# TvsTester.net
KiCad netlist of a schematic drawn in Altium Designer
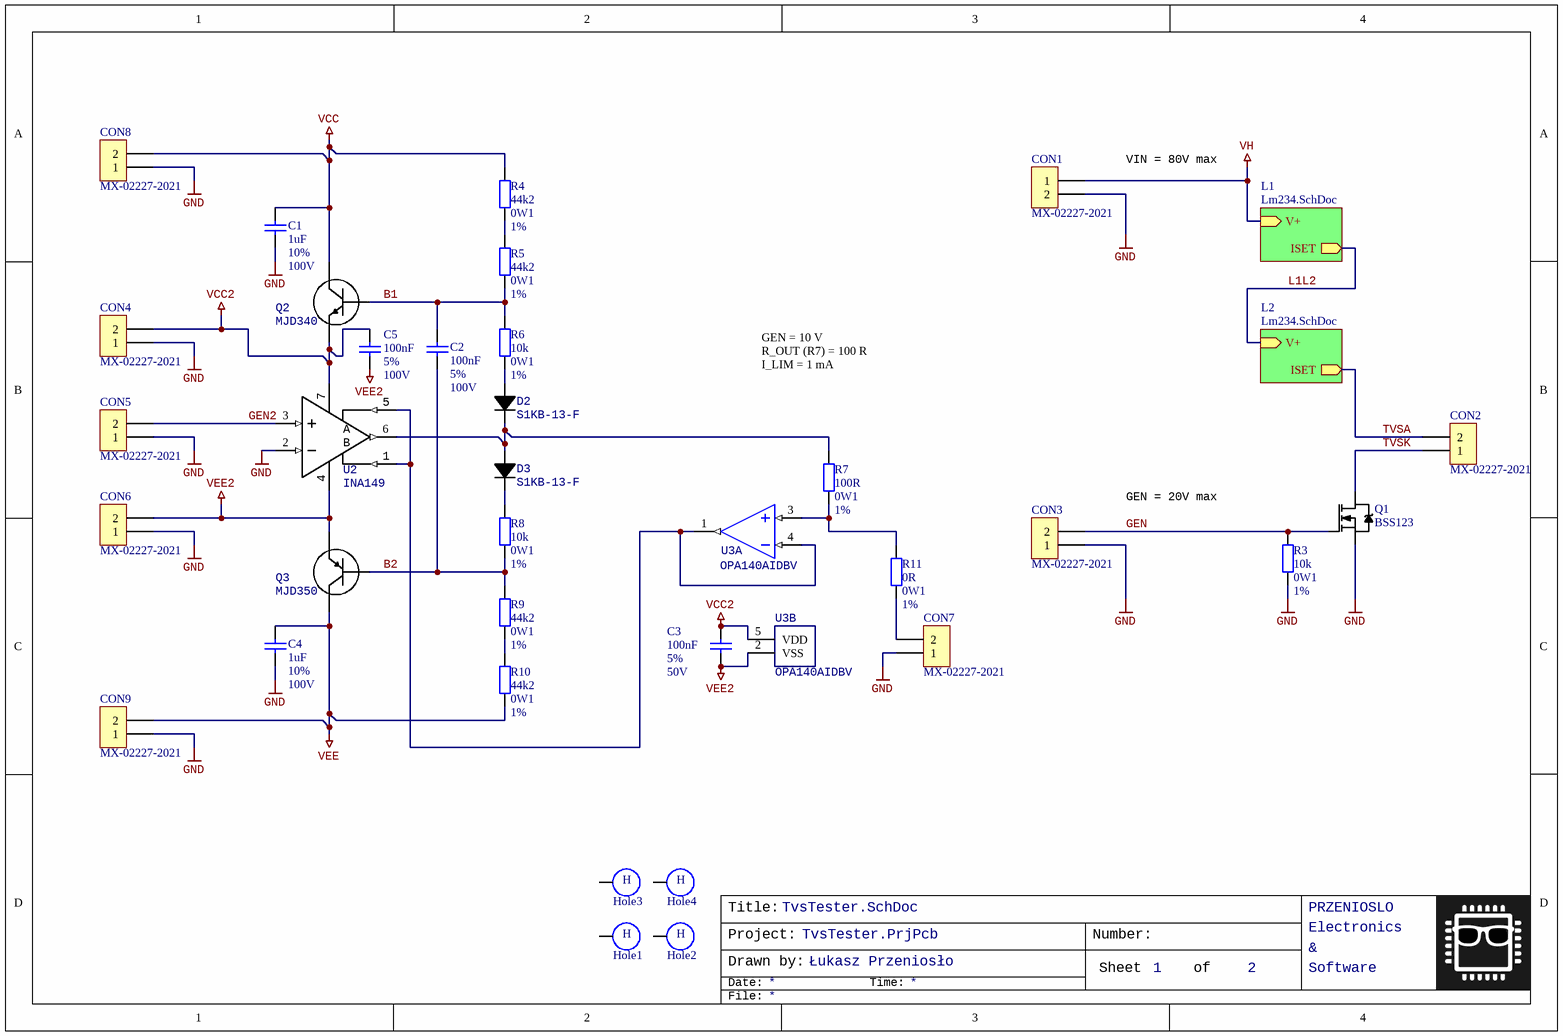
[diagram p0: TvsTester.SchDoc]

(export (version "E")
  (design (tool "Eeschema 10.0.6"))
  (components
    (comp (ref "C1")
      (value "1uF")
      (footprint "CAPC3225N")
      (description "Capacitor")
      (fields (field (name "TOLERANCE") "10%") (field (name "VOLTAGE") "100V"))
      (libsource (lib "passives") (part "Capacitor"))
    )
    (comp (ref "C2")
      (value "100nF")
      (footprint "CAPC3216N")
      (description "Capacitor")
      (fields (field (name "TOLERANCE") "5%") (field (name "VOLTAGE") "100V"))
      (libsource (lib "passives") (part "Capacitor"))
    )
    (comp (ref "C3")
      (value "100nF")
      (footprint "CAPC1608N")
      (description "Capacitor")
      (fields (field (name "TOLERANCE") "5%") (field (name "VOLTAGE") "50V"))
      (libsource (lib "passives") (part "Capacitor"))
    )
    (comp (ref "C4")
      (value "1uF")
      (footprint "CAPC3225N")
      (description "Capacitor")
      (fields (field (name "TOLERANCE") "10%") (field (name "VOLTAGE") "100V"))
      (libsource (lib "passives") (part "Capacitor"))
    )
    (comp (ref "C5")
      (value "100nF")
      (footprint "CAPC3216N")
      (description "Capacitor")
      (fields (field (name "TOLERANCE") "5%") (field (name "VOLTAGE") "100V"))
      (libsource (lib "passives") (part "Capacitor"))
    )
    (comp (ref "CON1")
      (value "MX-02227-2021")
      (footprint "MX-02227-2021")
      (description "Pith 2.54mm, 2-pin")
      (libsource (lib "") (part "MX-02227-2021_2"))
    )
    (comp (ref "CON2")
      (value "MX-02227-2021")
      (footprint "MX-02227-2021")
      (description "Pith 2.54mm, 2-pin")
      (libsource (lib "") (part "MX-02227-2021_1"))
    )
    (comp (ref "CON3")
      (value "MX-02227-2021")
      (footprint "MX-02227-2021")
      (description "Pith 2.54mm, 2-pin")
      (libsource (lib "connectors") (part "MX-02227-2021"))
    )
    (comp (ref "CON4")
      (value "MX-02227-2021")
      (footprint "MX-02227-2021")
      (description "Pith 2.54mm, 2-pin")
      (libsource (lib "connectors") (part "MX-02227-2021"))
    )
    (comp (ref "CON5")
      (value "MX-02227-2021")
      (footprint "MX-02227-2021")
      (description "Pith 2.54mm, 2-pin")
      (libsource (lib "connectors") (part "MX-02227-2021"))
    )
    (comp (ref "CON6")
      (value "MX-02227-2021")
      (footprint "MX-02227-2021")
      (description "Pith 2.54mm, 2-pin")
      (libsource (lib "connectors") (part "MX-02227-2021"))
    )
    (comp (ref "CON7")
      (value "MX-02227-2021")
      (footprint "MX-02227-2021")
      (description "Pith 2.54mm, 2-pin")
      (libsource (lib "") (part "MX-02227-2021_1"))
    )
    (comp (ref "CON8")
      (value "MX-02227-2021")
      (footprint "MX-02227-2021")
      (description "Pith 2.54mm, 2-pin")
      (libsource (lib "connectors") (part "MX-02227-2021"))
    )
    (comp (ref "CON9")
      (value "MX-02227-2021")
      (footprint "MX-02227-2021")
      (description "Pith 2.54mm, 2-pin")
      (libsource (lib "connectors") (part "MX-02227-2021"))
    )
    (comp (ref "D2")
      (value "S1KB-13-F")
      (footprint "SMB")
      (description "Universal diode")
      (libsource (lib "semicon") (part "S1KB-13-F"))
    )
    (comp (ref "D3")
      (value "S1KB-13-F")
      (footprint "SMB")
      (description "Universal diode")
      (libsource (lib "semicon") (part "S1KB-13-F"))
    )
    (comp (ref "Hole1") (value "Hole") (footprint "HOLE-6/3.2") (libsource (lib "misc") (part "HOLE_")))
    (comp (ref "Hole2") (value "Hole") (footprint "HOLE-6/3.2") (libsource (lib "misc") (part "HOLE_")))
    (comp (ref "Hole3") (value "Hole") (footprint "HOLE-6/3.2") (libsource (lib "misc") (part "HOLE_")))
    (comp (ref "Hole4") (value "Hole") (footprint "HOLE-6/3.2") (libsource (lib "misc") (part "HOLE_")))
    (comp (ref "Q1") (value "BSS123") (footprint "sot23-3l") (libsource (lib "semicon") (part "BSS123")))
    (comp (ref "Q2")
      (value "MJD340")
      (footprint "DPAK_TO252 _1SIDE")
      (description "High voltage NPN power transistor")
      (libsource (lib "semicon") (part "MJD340"))
    )
    (comp (ref "Q3")
      (value "MJD350")
      (footprint "DPAK_TO252 _1SIDE")
      (description "High voltage PNP power transistor")
      (libsource (lib "semicon") (part "MJD350"))
    )
    (comp (ref "R3")
      (value "10k")
      (footprint "RESC1608N")
      (description "Resistor")
      (fields (field (name "POWER") "0W1") (field (name "TOLERANCE") "1%"))
      (libsource (lib "passives") (part "Resistor"))
    )
    (comp (ref "R4")
      (value "44k2")
      (footprint "RESC1608N")
      (description "Resistor")
      (fields (field (name "POWER") "0W1") (field (name "TOLERANCE") "1%"))
      (libsource (lib "passives") (part "Resistor"))
    )
    (comp (ref "R5")
      (value "44k2")
      (footprint "RESC1608N")
      (description "Resistor")
      (fields (field (name "POWER") "0W1") (field (name "TOLERANCE") "1%"))
      (libsource (lib "passives") (part "Resistor"))
    )
    (comp (ref "R6")
      (value "10k")
      (footprint "RESC1608N")
      (description "Resistor")
      (fields (field (name "POWER") "0W1") (field (name "TOLERANCE") "1%"))
      (libsource (lib "passives") (part "Resistor"))
    )
    (comp (ref "R7")
      (value "100R")
      (footprint "RESC3216N")
      (description "Resistor")
      (fields (field (name "POWER") "0W1") (field (name "TOLERANCE") "1%"))
      (libsource (lib "passives") (part "Resistor"))
    )
    (comp (ref "R8")
      (value "10k")
      (footprint "RESC1608N")
      (description "Resistor")
      (fields (field (name "POWER") "0W1") (field (name "TOLERANCE") "1%"))
      (libsource (lib "passives") (part "Resistor"))
    )
    (comp (ref "R9")
      (value "44k2")
      (footprint "RESC1608N")
      (description "Resistor")
      (fields (field (name "POWER") "0W1") (field (name "TOLERANCE") "1%"))
      (libsource (lib "passives") (part "Resistor"))
    )
    (comp (ref "R10")
      (value "44k2")
      (footprint "RESC1608N")
      (description "Resistor")
      (fields (field (name "POWER") "0W1") (field (name "TOLERANCE") "1%"))
      (libsource (lib "passives") (part "Resistor"))
    )
    (comp (ref "R11")
      (value "0R")
      (footprint "RESC3216N")
      (description "Resistor")
      (fields (field (name "POWER") "0W1") (field (name "TOLERANCE") "1%"))
      (libsource (lib "passives") (part "Resistor"))
    )
    (comp (ref "U2")
      (value "INA149")
      (footprint "SO-8_L")
      (description "High Common-Mode Voltage Difference Amplifier")
      (libsource (lib "analog") (part "INA149"))
    )
    (comp (ref "U3")
      (value "OPA140AIDBV")
      (footprint "SOT23-5_N")
      (description "1 MHz, Low-Power Op Amp")
      (libsource (lib "") (part "OPA140_1"))
    )
  )
  (nets
    (net (code "1") (name "/B1") (class "Default")
      (node (ref "C2") (pin "2") (pinfunction "2_2") (pintype "passive"))
      (node (ref "Q2") (pin "1") (pinfunction "B_1") (pintype "passive"))
      (node (ref "R5") (pin "1") (pinfunction "1_1") (pintype "passive"))
      (node (ref "R6") (pin "2") (pinfunction "2_2") (pintype "passive"))
    )
    (net (code "2") (name "/B2") (class "Default")
      (node (ref "C2") (pin "1") (pinfunction "1_1") (pintype "passive"))
      (node (ref "Q3") (pin "1") (pinfunction "B_1") (pintype "passive"))
      (node (ref "R8") (pin "1") (pinfunction "1_1") (pintype "passive"))
      (node (ref "R9") (pin "2") (pinfunction "2_2") (pintype "passive"))
    )
    (net (code "3") (name "/GEN") (class "Default")
      (node (ref "CON3") (pin "2") (pinfunction "2_2") (pintype "passive"))
      (node (ref "Q1") (pin "1") (pinfunction "G_1") (pintype "passive"))
      (node (ref "R3") (pin "2") (pinfunction "2_2") (pintype "passive"))
    )
    (net (code "4") (name "/GEN2") (class "Default")
      (node (ref "CON5") (pin "2") (pinfunction "2_2") (pintype "passive"))
      (node (ref "U2") (pin "3") (pinfunction "+IN_3") (pintype "input"))
    )
    (net (code "6") (name "/TVSA") (class "Default")
      (node (ref "CON2") (pin "2") (pinfunction "2_2") (pintype "passive"))
    )
    (net (code "7") (name "/TVSK") (class "Default")
      (node (ref "CON2") (pin "1") (pinfunction "1_1") (pintype "passive"))
      (node (ref "Q1") (pin "3") (pinfunction "D_3") (pintype "passive"))
    )
    (net (code "8") (name "GND") (class "Default")
      (node (ref "C1") (pin "1") (pinfunction "1_1") (pintype "passive"))
      (node (ref "C4") (pin "1") (pinfunction "1_1") (pintype "passive"))
      (node (ref "CON1") (pin "2") (pinfunction "2_2") (pintype "passive"))
      (node (ref "CON3") (pin "1") (pinfunction "1_1") (pintype "passive"))
      (node (ref "CON4") (pin "1") (pinfunction "1_1") (pintype "passive"))
      (node (ref "CON5") (pin "1") (pinfunction "1_1") (pintype "passive"))
      (node (ref "CON6") (pin "1") (pinfunction "1_1") (pintype "passive"))
      (node (ref "CON7") (pin "1") (pinfunction "1_1") (pintype "passive"))
      (node (ref "CON8") (pin "1") (pinfunction "1_1") (pintype "passive"))
      (node (ref "CON9") (pin "1") (pinfunction "1_1") (pintype "passive"))
      (node (ref "Q1") (pin "2") (pinfunction "S_2") (pintype "passive"))
      (node (ref "R3") (pin "1") (pinfunction "1_1") (pintype "passive"))
      (node (ref "U2") (pin "2") (pinfunction "-IN_2") (pintype "input"))
    )
    (net (code "9") (name "Net-(CON7-Pad2)") (class "Default")
      (node (ref "CON7") (pin "2") (pinfunction "2_2") (pintype "passive"))
      (node (ref "R11") (pin "1") (pinfunction "1_1") (pintype "passive"))
    )
    (net (code "10") (name "Net-(D2-A)") (class "Default")
      (node (ref "D2") (pin "1") (pinfunction "A_1") (pintype "passive"))
      (node (ref "R6") (pin "1") (pinfunction "1_1") (pintype "passive"))
    )
    (net (code "11") (name "Net-(D2-K)") (class "Default")
      (node (ref "D2") (pin "2") (pinfunction "K_2") (pintype "passive"))
      (node (ref "D3") (pin "1") (pinfunction "A_1") (pintype "passive"))
      (node (ref "R7") (pin "2") (pinfunction "2_2") (pintype "passive"))
      (node (ref "U2") (pin "6") (pinfunction "VOUT_6") (pintype "output"))
    )
    (net (code "12") (name "Net-(D3-K)") (class "Default")
      (node (ref "D3") (pin "2") (pinfunction "K_2") (pintype "passive"))
      (node (ref "R8") (pin "2") (pinfunction "2_2") (pintype "passive"))
    )
    (net (code "13") (name "Net-(R4-Pad1)") (class "Default")
      (node (ref "R4") (pin "1") (pinfunction "1_1") (pintype "passive"))
      (node (ref "R5") (pin "2") (pinfunction "2_2") (pintype "passive"))
    )
    (net (code "14") (name "Net-(R10-Pad2)") (class "Default")
      (node (ref "R10") (pin "2") (pinfunction "2_2") (pintype "passive"))
      (node (ref "R9") (pin "1") (pinfunction "1_1") (pintype "passive"))
    )
    (net (code "15") (name "Net-(U2-REFA)") (class "Default")
      (node (ref "U2") (pin "1") (pinfunction "REFB_1") (pintype "input"))
      (node (ref "U2") (pin "5") (pinfunction "REFA_5") (pintype "input"))
      (node (ref "U3") (pin "1") (pinfunction "OUT_1") (pintype "output"))
      (node (ref "U3") (pin "4") (pinfunction "-IN_4") (pintype "input"))
    )
    (net (code "16") (name "Net-(U3A-+IN)") (class "Default")
      (node (ref "R11") (pin "2") (pinfunction "2_2") (pintype "passive"))
      (node (ref "R7") (pin "1") (pinfunction "1_1") (pintype "passive"))
      (node (ref "U3") (pin "3") (pinfunction "+IN_3") (pintype "input"))
    )
    (net (code "17") (name "VCC") (class "Default")
      (node (ref "C1") (pin "2") (pinfunction "2_2") (pintype "passive"))
      (node (ref "CON8") (pin "2") (pinfunction "2_2") (pintype "passive"))
      (node (ref "Q2") (pin "2") (pinfunction "C_2") (pintype "open_collector"))
      (node (ref "R4") (pin "2") (pinfunction "2_2") (pintype "passive"))
    )
    (net (code "18") (name "VCC2") (class "Default")
      (node (ref "C3") (pin "2") (pinfunction "2_2") (pintype "passive"))
      (node (ref "C5") (pin "2") (pinfunction "2_2") (pintype "passive"))
      (node (ref "CON4") (pin "2") (pinfunction "2_2") (pintype "passive"))
      (node (ref "Q2") (pin "3") (pinfunction "E_3") (pintype "passive"))
      (node (ref "U2") (pin "7") (pinfunction "V+_7") (pintype "power_in"))
      (node (ref "U3") (pin "5") (pinfunction "VDD_5") (pintype "power_in"))
    )
    (net (code "19") (name "VEE") (class "Default")
      (node (ref "C4") (pin "2") (pinfunction "2_2") (pintype "passive"))
      (node (ref "CON9") (pin "2") (pinfunction "2_2") (pintype "passive"))
      (node (ref "Q3") (pin "2") (pinfunction "C_2") (pintype "open_collector"))
      (node (ref "R10") (pin "1") (pinfunction "1_1") (pintype "passive"))
    )
    (net (code "20") (name "VEE2") (class "Default")
      (node (ref "C3") (pin "1") (pinfunction "1_1") (pintype "passive"))
      (node (ref "C5") (pin "1") (pinfunction "1_1") (pintype "passive"))
      (node (ref "CON6") (pin "2") (pinfunction "2_2") (pintype "passive"))
      (node (ref "Q3") (pin "3") (pinfunction "E_3") (pintype "passive"))
      (node (ref "U2") (pin "4") (pinfunction "VS-_4") (pintype "power_in"))
      (node (ref "U3") (pin "2") (pinfunction "VSS_2") (pintype "power_in"))
    )
    (net (code "21") (name "VH") (class "Default")
      (node (ref "CON1") (pin "1") (pinfunction "1_1") (pintype "passive"))
    )
    (net (code "22") (name "unconnected-(Hole1-Pad1)") (class "Default")
      (node (ref "Hole1") (pin "1") (pinfunction "1_1") (pintype "passive"))
    )
    (net (code "23") (name "unconnected-(Hole2-Pad1)") (class "Default")
      (node (ref "Hole2") (pin "1") (pinfunction "1_1") (pintype "passive"))
    )
    (net (code "24") (name "unconnected-(Hole3-Pad1)") (class "Default")
      (node (ref "Hole3") (pin "1") (pinfunction "1_1") (pintype "passive"))
    )
    (net (code "25") (name "unconnected-(Hole4-Pad1)") (class "Default")
      (node (ref "Hole4") (pin "1") (pinfunction "1_1") (pintype "passive"))
    )
    (net (code "26") (name "unconnected-(U2-NC-Pad8)") (class "Default")
      (node (ref "U2") (pin "8") (pinfunction "NC_8") (pintype "passive"))
    )
  )
)
